# AES3_Transceiver.net
KiCad netlist of a schematic drawn in Altium Designer
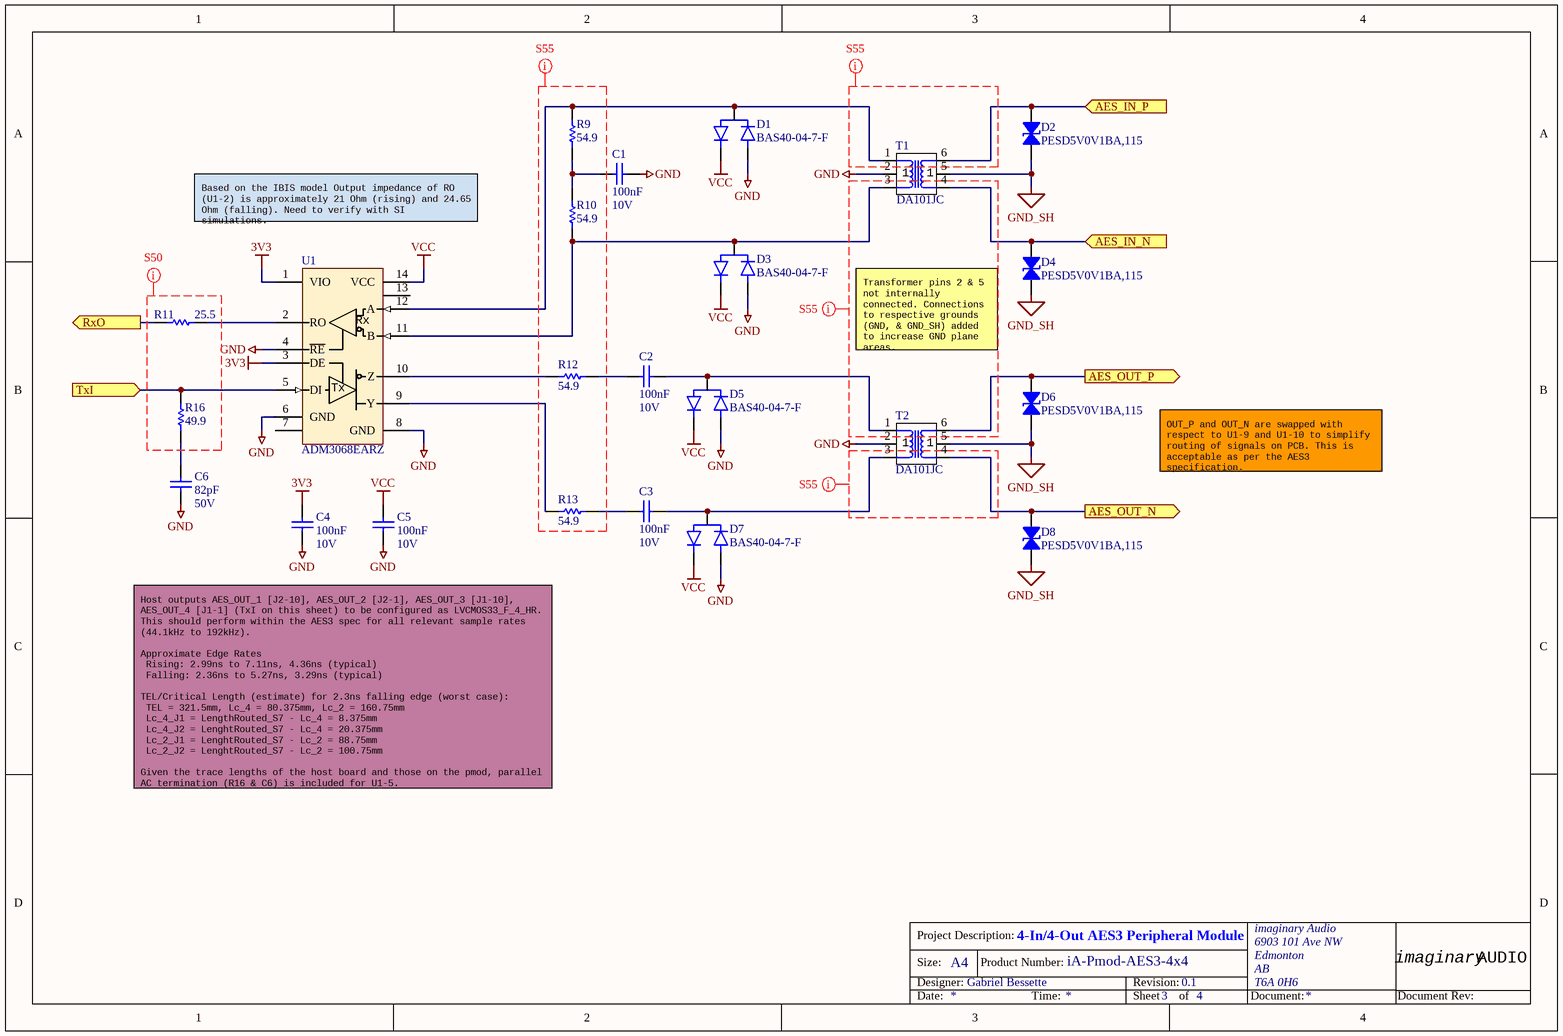
[diagram p0: AES3_Transceiver.SchDoc]

(export (version "E")
  (design (tool "Eeschema 10.0.6"))
  (components
    (comp (ref "C1")
      (value "100nF")
      (footprint "CAPC0603(1608)100_N")
      (fields
        (field (name "MANUFACTURER") "KEMET")
        (field (name "MANUFACTURER PART NUMBER") "C0603C104K8RACTU")
        (field (name "TOLERANCE") "10%")
        (field (name "VOLTAGE") "10V")
      )
      (libsource (lib "iA-IntLib") (part "CAP"))
    )
    (comp (ref "C2")
      (value "100nF")
      (footprint "CAPC0603(1608)100_N")
      (fields
        (field (name "MANUFACTURER") "KEMET")
        (field (name "MANUFACTURER PART NUMBER") "C0603C104K8RACTU")
        (field (name "TOLERANCE") "10%")
        (field (name "VOLTAGE") "10V")
      )
      (libsource (lib "iA-IntLib") (part "CAP"))
    )
    (comp (ref "C3")
      (value "100nF")
      (footprint "CAPC0603(1608)100_N")
      (fields
        (field (name "MANUFACTURER") "KEMET")
        (field (name "MANUFACTURER PART NUMBER") "C0603C104K8RACTU")
        (field (name "TOLERANCE") "10%")
        (field (name "VOLTAGE") "10V")
      )
      (libsource (lib "iA-IntLib") (part "CAP"))
    )
    (comp (ref "C4")
      (value "100nF")
      (footprint "CAPC0603(1608)100_N")
      (fields
        (field (name "MANUFACTURER") "KEMET")
        (field (name "MANUFACTURER PART NUMBER") "C0603C104K8RACTU")
        (field (name "TOLERANCE") "10%")
        (field (name "VOLTAGE") "10V")
      )
      (libsource (lib "iA-IntLib") (part "CAP"))
    )
    (comp (ref "C5")
      (value "100nF")
      (footprint "CAPC0603(1608)100_N")
      (fields
        (field (name "MANUFACTURER") "KEMET")
        (field (name "MANUFACTURER PART NUMBER") "C0603C104K8RACTU")
        (field (name "TOLERANCE") "10%")
        (field (name "VOLTAGE") "10V")
      )
      (libsource (lib "iA-IntLib") (part "CAP"))
    )
    (comp (ref "C6")
      (value "82pF")
      (footprint "CAPC0603(1608)100_N")
      (fields
        (field (name "MANUFACTURER") "KEMET")
        (field (name "MANUFACTURER PART NUMBER") "C0603C820J5GACTU")
        (field (name "TOLERANCE") "5%")
        (field (name "VOLTAGE") "50V")
      )
      (libsource (lib "iA-IntLib") (part "CAP"))
    )
    (comp (ref "D1")
      (value "BAS40-04-7-F")
      (footprint "FP-SOT23-MFG")
      (description "DIODE SCHOTTKY 40V 350MW SOT23-3")
      (fields
        (field (name "MANUFACTURER") "Diodes Inc.")
        (field (name "OCTOPART") "https://octopart.com/bas40-04-7-f-diodes+inc.-325979")
      )
      (libsource (lib "iA-SchLib") (part "BAS40-04-7-F"))
    )
    (comp (ref "D2")
      (value "PESD5V0V1BA,115")
      (footprint "SOD323")
      (description "TVS DIODE 5V 12.5V SOD323")
      (fields (field (name "MANUFACTURER") "Nexperia USA Inc."))
      (libsource (lib "Celestial Altium Library - altium_library") (part "Diode TVS"))
    )
    (comp (ref "D3")
      (value "BAS40-04-7-F")
      (footprint "FP-SOT23-MFG")
      (description "DIODE SCHOTTKY 40V 350MW SOT23-3")
      (fields
        (field (name "MANUFACTURER") "Diodes Inc.")
        (field (name "OCTOPART") "https://octopart.com/bas40-04-7-f-diodes+inc.-325979")
      )
      (libsource (lib "iA-SchLib") (part "BAS40-04-7-F"))
    )
    (comp (ref "D4")
      (value "PESD5V0V1BA,115")
      (footprint "SOD323")
      (description "TVS DIODE 5V 12.5V SOD323")
      (fields (field (name "MANUFACTURER") "Nexperia USA Inc."))
      (libsource (lib "Celestial Altium Library - altium_library") (part "Diode TVS"))
    )
    (comp (ref "D5")
      (value "BAS40-04-7-F")
      (footprint "FP-SOT23-MFG")
      (description "DIODE SCHOTTKY 40V 350MW SOT23-3")
      (fields
        (field (name "MANUFACTURER") "Diodes Inc.")
        (field (name "OCTOPART") "https://octopart.com/bas40-04-7-f-diodes+inc.-325979")
      )
      (libsource (lib "iA-SchLib") (part "BAS40-04-7-F"))
    )
    (comp (ref "D6")
      (value "PESD5V0V1BA,115")
      (footprint "SOD323")
      (description "TVS DIODE 5V 12.5V SOD323")
      (fields (field (name "MANUFACTURER") "Nexperia USA Inc."))
      (libsource (lib "Celestial Altium Library - altium_library") (part "Diode TVS"))
    )
    (comp (ref "D7")
      (value "BAS40-04-7-F")
      (footprint "FP-SOT23-MFG")
      (description "DIODE SCHOTTKY 40V 350MW SOT23-3")
      (fields
        (field (name "MANUFACTURER") "Diodes Inc.")
        (field (name "OCTOPART") "https://octopart.com/bas40-04-7-f-diodes+inc.-325979")
      )
      (libsource (lib "iA-SchLib") (part "BAS40-04-7-F"))
    )
    (comp (ref "D8")
      (value "PESD5V0V1BA,115")
      (footprint "SOD323")
      (description "TVS DIODE 5V 12.5V SOD323")
      (fields (field (name "MANUFACTURER") "Nexperia USA Inc."))
      (libsource (lib "Celestial Altium Library - altium_library") (part "Diode TVS"))
    )
    (comp (ref "R9")
      (value "54.9")
      (footprint "RESC1608X55X30NL15T15")
      (fields (field (name "MANUFACTURER PART NUMBER") "ERJ-3EKF54R9V") (field (name "TOLERANCE") "1%"))
      (libsource (lib "iA-IntLib") (part "RES"))
    )
    (comp (ref "R10")
      (value "54.9")
      (footprint "RESC1608X55X30NL15T15")
      (fields (field (name "MANUFACTURER PART NUMBER") "ERJ-3EKF54R9V") (field (name "TOLERANCE") "1%"))
      (libsource (lib "iA-IntLib") (part "RES"))
    )
    (comp (ref "R11")
      (value "25.5")
      (footprint "RESC1608X55X30NL15T15")
      (description "RES SMD 25.5 OHM 1% 1/10W 0603")
      (fields (field (name "MANUFACTURER PART NUMBER") "ERJ-3EKF25R5V") (field (name "TOLERANCE") "1%"))
      (libsource (lib "iA-IntLib") (part "RES"))
    )
    (comp (ref "R12")
      (value "54.9")
      (footprint "RESC1608X55X30NL15T15")
      (fields (field (name "MANUFACTURER PART NUMBER") "ERJ-3EKF54R9V") (field (name "TOLERANCE") "1%"))
      (libsource (lib "iA-IntLib") (part "RES"))
    )
    (comp (ref "R13")
      (value "54.9")
      (footprint "RESC1608X55X30NL15T15")
      (fields (field (name "MANUFACTURER PART NUMBER") "ERJ-3EKF54R9V") (field (name "TOLERANCE") "1%"))
      (libsource (lib "iA-IntLib") (part "RES"))
    )
    (comp (ref "R16")
      (value "49.9")
      (footprint "RESC1608X55X30NL15T15")
      (description "PANASONIC - ERJ-3EKF49R9V. - Resistor Case Style:0603 [1608 Metric]")
      (fields (field (name "MANUFACTURER PART NUMBER") "ERJ3EKF49R9V") (field (name "TOLERANCE") "1%"))
      (libsource (lib "iA-IntLib") (part "RES"))
    )
    (comp (ref "T1")
      (value "DA101JC")
      (footprint "DA101JC")
      (description "TRANS, Digital Audio 1:1 2000Vrms 6Term. Gull Wing SMD")
      (fields (field (name "MANUFACTURER") "Murata"))
      (libsource (lib "iA-IntLib") (part "DA101JC"))
    )
    (comp (ref "T2")
      (value "DA101JC")
      (footprint "DA101JC")
      (description "TRANS, Digital Audio 1:1 2000Vrms 6Term. Gull Wing SMD")
      (fields (field (name "MANUFACTURER") "Murata"))
      (libsource (lib "iA-IntLib") (part "DA101JC"))
    )
    (comp (ref "U1")
      (value "ADM3068EARZ")
      (footprint "SOIC127P600X175-14N")
      (description "XCVR, Full-Duplex, RS-485, 50 Mbps")
      (fields
        (field (name "MANUFACTURER") "Analog Devices")
        (field (name "MANUFACTURER PART NUMBER") "ADM3068EARZ")
      )
      (libsource (lib "iA-SchLib") (part "ADM3068EARZ"))
    )
  )
  (nets
    (net (code "1") (name "/AES_IN_N") (class "Default")
      (node (ref "D4") (pin "1") (pinfunction "1_1") (pintype "passive"))
      (node (ref "T1") (pin "4") (pintype "passive"))
    )
    (net (code "2") (name "/AES_IN_P") (class "Default")
      (node (ref "D2") (pin "1") (pinfunction "1_1") (pintype "passive"))
      (node (ref "T1") (pin "6") (pintype "passive"))
    )
    (net (code "3") (name "/AES_OUT_N") (class "Default")
      (node (ref "D8") (pin "1") (pinfunction "1_1") (pintype "passive"))
      (node (ref "T2") (pin "4") (pintype "passive"))
    )
    (net (code "4") (name "/AES_OUT_P") (class "Default")
      (node (ref "D6") (pin "1") (pinfunction "1_1") (pintype "passive"))
      (node (ref "T2") (pin "6") (pintype "passive"))
    )
    (net (code "5") (name "/RxO") (class "Default")
      (node (ref "R11") (pin "1") (pinfunction "1_1") (pintype "passive"))
    )
    (net (code "6") (name "/TxI") (class "Default")
      (node (ref "R16") (pin "2") (pinfunction "2_2") (pintype "passive"))
      (node (ref "U1") (pin "5") (pinfunction "DI_5") (pintype "input"))
    )
    (net (code "7") (name "3V3") (class "Default")
      (node (ref "C4") (pin "2") (pinfunction "2_2") (pintype "passive"))
      (node (ref "U1") (pin "1") (pinfunction "VIO_1") (pintype "power_in"))
      (node (ref "U1") (pin "3") (pinfunction "DE_3") (pintype "passive"))
    )
    (net (code "8") (name "GND") (class "Default")
      (node (ref "C1") (pin "2") (pinfunction "2_2") (pintype "passive"))
      (node (ref "C4") (pin "1") (pinfunction "1_1") (pintype "passive"))
      (node (ref "C5") (pin "1") (pinfunction "1_1") (pintype "passive"))
      (node (ref "C6") (pin "1") (pinfunction "1_1") (pintype "passive"))
      (node (ref "D1") (pin "1") (pinfunction "1_1") (pintype "passive"))
      (node (ref "D3") (pin "1") (pinfunction "1_1") (pintype "passive"))
      (node (ref "D5") (pin "1") (pinfunction "1_1") (pintype "passive"))
      (node (ref "D7") (pin "1") (pinfunction "1_1") (pintype "passive"))
      (node (ref "T1") (pin "2") (pintype "passive"))
      (node (ref "T2") (pin "2") (pintype "passive"))
      (node (ref "U1") (pin "4") (pinfunction "~{RE}_4") (pintype "passive"))
      (node (ref "U1") (pin "6") (pinfunction "GND_6") (pintype "power_in"))
      (node (ref "U1") (pin "8") (pinfunction "GND_8") (pintype "power_in"))
    )
    (net (code "9") (name "GND_SH") (class "Default")
      (node (ref "D2") (pin "2") (pinfunction "2_2") (pintype "passive"))
      (node (ref "D4") (pin "2") (pinfunction "2_2") (pintype "passive"))
      (node (ref "D6") (pin "2") (pinfunction "2_2") (pintype "passive"))
      (node (ref "D8") (pin "2") (pinfunction "2_2") (pintype "passive"))
      (node (ref "T1") (pin "5") (pintype "passive"))
      (node (ref "T2") (pin "5") (pintype "passive"))
    )
    (net (code "10") (name "Net-(C1-Pad1)") (class "Default")
      (node (ref "C1") (pin "1") (pinfunction "1_1") (pintype "passive"))
      (node (ref "R10") (pin "2") (pinfunction "2_2") (pintype "passive"))
      (node (ref "R9") (pin "1") (pinfunction "1_1") (pintype "passive"))
    )
    (net (code "11") (name "Net-(C2-Pad1)") (class "Default")
      (node (ref "C2") (pin "1") (pinfunction "1_1") (pintype "passive"))
      (node (ref "R12") (pin "1") (pinfunction "1_1") (pintype "passive"))
    )
    (net (code "12") (name "Net-(C2-Pad2)") (class "Default")
      (node (ref "C2") (pin "2") (pinfunction "2_2") (pintype "passive"))
      (node (ref "D5") (pin "3") (pinfunction "3_3") (pintype "passive"))
      (node (ref "T2") (pin "1") (pintype "passive"))
    )
    (net (code "13") (name "Net-(C3-Pad1)") (class "Default")
      (node (ref "C3") (pin "1") (pinfunction "1_1") (pintype "passive"))
      (node (ref "R13") (pin "1") (pinfunction "1_1") (pintype "passive"))
    )
    (net (code "14") (name "Net-(C3-Pad2)") (class "Default")
      (node (ref "C3") (pin "2") (pinfunction "2_2") (pintype "passive"))
      (node (ref "D7") (pin "3") (pinfunction "3_3") (pintype "passive"))
      (node (ref "T2") (pin "3") (pintype "passive"))
    )
    (net (code "15") (name "Net-(C6-Pad2)") (class "Default")
      (node (ref "C6") (pin "2") (pinfunction "2_2") (pintype "passive"))
      (node (ref "R16") (pin "1") (pinfunction "1_1") (pintype "passive"))
    )
    (net (code "16") (name "Net-(U1-A)") (class "Default")
      (node (ref "D1") (pin "3") (pinfunction "3_3") (pintype "passive"))
      (node (ref "R9") (pin "2") (pinfunction "2_2") (pintype "passive"))
      (node (ref "T1") (pin "1") (pintype "passive"))
      (node (ref "U1") (pin "12") (pinfunction "A_12") (pintype "input"))
    )
    (net (code "17") (name "Net-(U1-B)") (class "Default")
      (node (ref "D3") (pin "3") (pinfunction "3_3") (pintype "passive"))
      (node (ref "R10") (pin "1") (pinfunction "1_1") (pintype "passive"))
      (node (ref "T1") (pin "3") (pintype "passive"))
      (node (ref "U1") (pin "11") (pinfunction "B_11") (pintype "input"))
    )
    (net (code "18") (name "Net-(U1-RO)") (class "Default")
      (node (ref "R11") (pin "2") (pinfunction "2_2") (pintype "passive"))
      (node (ref "U1") (pin "2") (pinfunction "RO_2") (pintype "tri_state"))
    )
    (net (code "19") (name "Net-(U1-Y)") (class "Default")
      (node (ref "R13") (pin "2") (pinfunction "2_2") (pintype "passive"))
      (node (ref "U1") (pin "9") (pinfunction "Y_9") (pintype "tri_state"))
    )
    (net (code "20") (name "Net-(U1-Z)") (class "Default")
      (node (ref "R12") (pin "2") (pinfunction "2_2") (pintype "passive"))
      (node (ref "U1") (pin "10") (pinfunction "Z_10") (pintype "tri_state"))
    )
    (net (code "21") (name "VCC") (class "Default")
      (node (ref "C5") (pin "2") (pinfunction "2_2") (pintype "passive"))
      (node (ref "D1") (pin "2") (pinfunction "2_2") (pintype "passive"))
      (node (ref "D3") (pin "2") (pinfunction "2_2") (pintype "passive"))
      (node (ref "D5") (pin "2") (pinfunction "2_2") (pintype "passive"))
      (node (ref "D7") (pin "2") (pinfunction "2_2") (pintype "passive"))
      (node (ref "U1") (pin "14") (pinfunction "VCC_14") (pintype "power_in"))
    )
    (net (code "22") (name "unconnected-(U1-NIC-Pad7)") (class "Default")
      (node (ref "U1") (pin "7") (pinfunction "NIC_7") (pintype "passive"))
    )
    (net (code "23") (name "unconnected-(U1-NIC-Pad13)") (class "Default")
      (node (ref "U1") (pin "13") (pinfunction "NIC_13") (pintype "passive"))
    )
  )
)
